# 20190404pcb.net
KiCad netlist of a schematic drawn in EAGLE
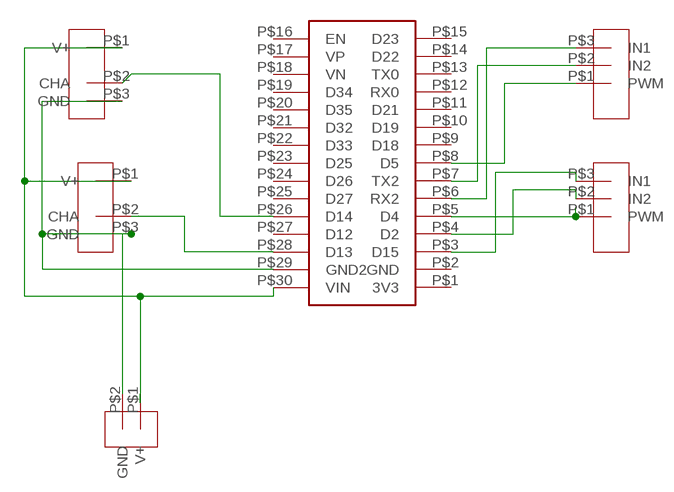
[diagram p0: schematic, sheet 1]

(export (version "E")
  (design (tool "Eeschema 10.0.6"))
  (components
    (comp (ref "LE")
      (value "ENCODER")
      (footprint "eagle-import:ENCODER")
      (libsource (lib "eagle-import") (part "ENCODER"))
    )
    (comp (ref "LM")
      (value "MOTORDRIVER")
      (footprint "eagle-import:MOTORDRIVER")
      (libsource (lib "eagle-import") (part "MOTORDRIVER"))
    )
    (comp (ref "RE")
      (value "ENCODER")
      (footprint "eagle-import:ENCODER")
      (libsource (lib "eagle-import") (part "ENCODER"))
    )
    (comp (ref "RM")
      (value "MOTORDRIVER")
      (footprint "eagle-import:MOTORDRIVER")
      (libsource (lib "eagle-import") (part "MOTORDRIVER"))
    )
    (comp (ref "U$1")
      (value "ESP32")
      (footprint "eagle-import:ESP32")
      (libsource (lib "eagle-import") (part "ESP32"))
    )
    (comp (ref "U$9")
      (value "SOURCE")
      (footprint "eagle-import:SOURCE")
      (libsource (lib "eagle-import") (part "SOURCE"))
    )
  )
  (nets
    (net (code "1") (name "Net-(LE-CHA)") (class "Default")
      (node (ref "LE") (pin "P$2") (pinfunction "CHA_P$2") (pintype "bidirectional"))
      (node (ref "U$1") (pin "P$28") (pinfunction "D13_P$28") (pintype "bidirectional"))
    )
    (net (code "2") (name "Net-(LE-GND)") (class "Default")
      (node (ref "LE") (pin "P$3") (pinfunction "GND_P$3") (pintype "bidirectional"))
      (node (ref "RE") (pin "P$3") (pinfunction "GND_P$3") (pintype "bidirectional"))
      (node (ref "U$1") (pin "P$29") (pinfunction "GND2_P$29") (pintype "bidirectional"))
      (node (ref "U$9") (pin "P$2") (pinfunction "GND_P$2") (pintype "bidirectional"))
    )
    (net (code "3") (name "Net-(LE-V+)") (class "Default")
      (node (ref "LE") (pin "P$1") (pinfunction "V+_P$1") (pintype "bidirectional"))
      (node (ref "RE") (pin "P$1") (pinfunction "V+_P$1") (pintype "bidirectional"))
      (node (ref "U$1") (pin "P$30") (pinfunction "VIN_P$30") (pintype "bidirectional"))
      (node (ref "U$9") (pin "P$1") (pinfunction "V+_P$1") (pintype "bidirectional"))
    )
    (net (code "4") (name "Net-(LM-IN1)") (class "Default")
      (node (ref "LM") (pin "P$3") (pinfunction "IN1_P$3") (pintype "bidirectional"))
      (node (ref "U$1") (pin "P$3") (pinfunction "D15_P$3") (pintype "bidirectional"))
    )
    (net (code "5") (name "Net-(LM-IN2)") (class "Default")
      (node (ref "LM") (pin "P$2") (pinfunction "IN2_P$2") (pintype "bidirectional"))
      (node (ref "U$1") (pin "P$4") (pinfunction "D2_P$4") (pintype "bidirectional"))
    )
    (net (code "6") (name "Net-(LM-PWM)") (class "Default")
      (node (ref "LM") (pin "P$1") (pinfunction "PWM_P$1") (pintype "bidirectional"))
      (node (ref "U$1") (pin "P$5") (pinfunction "D4_P$5") (pintype "bidirectional"))
    )
    (net (code "7") (name "Net-(RE-CHA)") (class "Default")
      (node (ref "RE") (pin "P$2") (pinfunction "CHA_P$2") (pintype "bidirectional"))
      (node (ref "U$1") (pin "P$26") (pinfunction "D14_P$26") (pintype "bidirectional"))
    )
    (net (code "8") (name "Net-(RM-IN1)") (class "Default")
      (node (ref "RM") (pin "P$3") (pinfunction "IN1_P$3") (pintype "bidirectional"))
      (node (ref "U$1") (pin "P$6") (pinfunction "RX2_P$6") (pintype "bidirectional"))
    )
    (net (code "9") (name "Net-(RM-IN2)") (class "Default")
      (node (ref "RM") (pin "P$2") (pinfunction "IN2_P$2") (pintype "bidirectional"))
      (node (ref "U$1") (pin "P$7") (pinfunction "TX2_P$7") (pintype "bidirectional"))
    )
    (net (code "10") (name "Net-(RM-PWM)") (class "Default")
      (node (ref "RM") (pin "P$1") (pinfunction "PWM_P$1") (pintype "bidirectional"))
      (node (ref "U$1") (pin "P$8") (pinfunction "D5_P$8") (pintype "bidirectional"))
    )
    (net (code "11") (name "unconnected-(U$1-3V3-PadP$1)") (class "Default")
      (node (ref "U$1") (pin "P$1") (pinfunction "3V3_P$1") (pintype "bidirectional"))
    )
    (net (code "12") (name "unconnected-(U$1-D12-PadP$27)") (class "Default")
      (node (ref "U$1") (pin "P$27") (pinfunction "D12_P$27") (pintype "bidirectional"))
    )
    (net (code "13") (name "unconnected-(U$1-D18-PadP$9)") (class "Default")
      (node (ref "U$1") (pin "P$9") (pinfunction "D18_P$9") (pintype "bidirectional"))
    )
    (net (code "14") (name "unconnected-(U$1-D19-PadP$10)") (class "Default")
      (node (ref "U$1") (pin "P$10") (pinfunction "D19_P$10") (pintype "bidirectional"))
    )
    (net (code "15") (name "unconnected-(U$1-D21-PadP$11)") (class "Default")
      (node (ref "U$1") (pin "P$11") (pinfunction "D21_P$11") (pintype "bidirectional"))
    )
    (net (code "16") (name "unconnected-(U$1-D22-PadP$14)") (class "Default")
      (node (ref "U$1") (pin "P$14") (pinfunction "D22_P$14") (pintype "bidirectional"))
    )
    (net (code "17") (name "unconnected-(U$1-D23-PadP$15)") (class "Default")
      (node (ref "U$1") (pin "P$15") (pinfunction "D23_P$15") (pintype "bidirectional"))
    )
    (net (code "18") (name "unconnected-(U$1-D25-PadP$23)") (class "Default")
      (node (ref "U$1") (pin "P$23") (pinfunction "D25_P$23") (pintype "bidirectional"))
    )
    (net (code "19") (name "unconnected-(U$1-D26-PadP$24)") (class "Default")
      (node (ref "U$1") (pin "P$24") (pinfunction "D26_P$24") (pintype "bidirectional"))
    )
    (net (code "20") (name "unconnected-(U$1-D27-PadP$25)") (class "Default")
      (node (ref "U$1") (pin "P$25") (pinfunction "D27_P$25") (pintype "bidirectional"))
    )
    (net (code "21") (name "unconnected-(U$1-D32-PadP$21)") (class "Default")
      (node (ref "U$1") (pin "P$21") (pinfunction "D32_P$21") (pintype "bidirectional"))
    )
    (net (code "22") (name "unconnected-(U$1-D33-PadP$22)") (class "Default")
      (node (ref "U$1") (pin "P$22") (pinfunction "D33_P$22") (pintype "bidirectional"))
    )
    (net (code "23") (name "unconnected-(U$1-D34-PadP$19)") (class "Default")
      (node (ref "U$1") (pin "P$19") (pinfunction "D34_P$19") (pintype "bidirectional"))
    )
    (net (code "24") (name "unconnected-(U$1-D35-PadP$20)") (class "Default")
      (node (ref "U$1") (pin "P$20") (pinfunction "D35_P$20") (pintype "bidirectional"))
    )
    (net (code "25") (name "unconnected-(U$1-EN-PadP$16)") (class "Default")
      (node (ref "U$1") (pin "P$16") (pinfunction "EN_P$16") (pintype "bidirectional"))
    )
    (net (code "26") (name "unconnected-(U$1-GND-PadP$2)") (class "Default")
      (node (ref "U$1") (pin "P$2") (pinfunction "GND_P$2") (pintype "bidirectional"))
    )
    (net (code "27") (name "unconnected-(U$1-RX0-PadP$12)") (class "Default")
      (node (ref "U$1") (pin "P$12") (pinfunction "RX0_P$12") (pintype "bidirectional"))
    )
    (net (code "28") (name "unconnected-(U$1-TX0-PadP$13)") (class "Default")
      (node (ref "U$1") (pin "P$13") (pinfunction "TX0_P$13") (pintype "bidirectional"))
    )
    (net (code "29") (name "unconnected-(U$1-VN-PadP$18)") (class "Default")
      (node (ref "U$1") (pin "P$18") (pinfunction "VN_P$18") (pintype "bidirectional"))
    )
    (net (code "30") (name "unconnected-(U$1-VP-PadP$17)") (class "Default")
      (node (ref "U$1") (pin "P$17") (pinfunction "VP_P$17") (pintype "bidirectional"))
    )
  )
)
